# design.net
KiCad netlist of a schematic drawn in Altium Designer
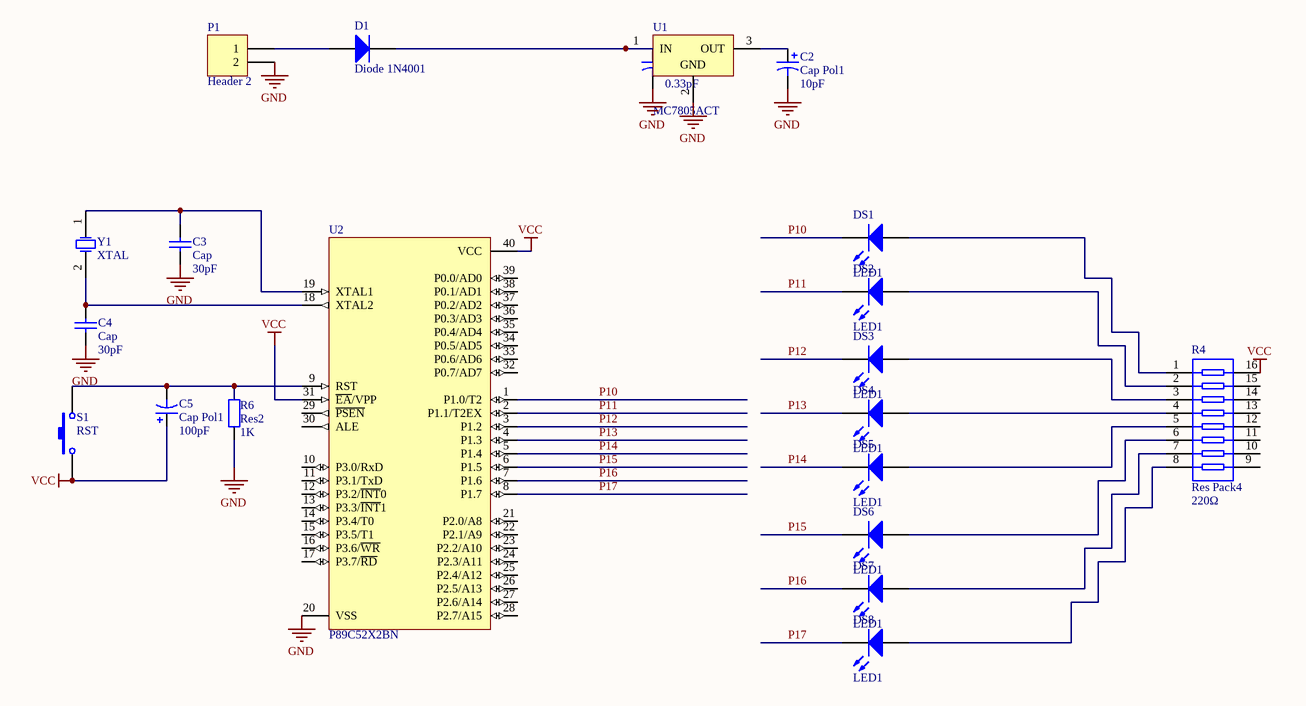
[diagram p0: 单片机控制流水灯电路.SchDoc]

(export (version "E")
  (design (tool "Eeschema 10.0.6"))
  (components
    (comp (ref "C1")
      (value "Cap Pol1")
      (footprint "RB7.6-15")
      (description "Polarized Capacitor (Radial)")
      (fields (field (name "ALTIUM_VALUE") "0.33pF") (field (name "PUBLISHER") "Altium Limited"))
      (libsource (lib "Miscellaneous Devices") (part "Cap Pol1"))
    )
    (comp (ref "C2")
      (value "Cap Pol1")
      (footprint "RB7.6-15")
      (description "Polarized Capacitor (Radial)")
      (fields (field (name "ALTIUM_VALUE") "10pF") (field (name "PUBLISHER") "Altium Limited"))
      (libsource (lib "Miscellaneous Devices") (part "Cap Pol1"))
    )
    (comp (ref "C3")
      (value "Cap")
      (footprint "RAD-0.3")
      (description "Capacitor")
      (fields (field (name "ALTIUM_VALUE") "30pF") (field (name "PUBLISHER") "Altium Limited"))
      (libsource (lib "Miscellaneous Devices") (part "Cap"))
    )
    (comp (ref "C4")
      (value "Cap")
      (footprint "RAD-0.3")
      (description "Capacitor")
      (fields (field (name "ALTIUM_VALUE") "30pF") (field (name "PUBLISHER") "Altium Limited"))
      (libsource (lib "Miscellaneous Devices") (part "Cap"))
    )
    (comp (ref "C5")
      (value "Cap Pol1")
      (footprint "RB7.6-15")
      (description "Polarized Capacitor (Radial)")
      (fields (field (name "ALTIUM_VALUE") "100pF") (field (name "PUBLISHER") "Altium Limited"))
      (libsource (lib "Miscellaneous Devices") (part "Cap Pol1"))
    )
    (comp (ref "D1")
      (value "Diode 1N4001")
      (footprint "DO-41")
      (description "1 Amp General Purpose Rectifier")
      (fields (field (name "PUBLISHER") "Altium Limited"))
      (libsource (lib "Miscellaneous Devices") (part "Diode 1N4001"))
    )
    (comp (ref "DS1")
      (value "LED1")
      (footprint "LED-1")
      (description "Typical RED GaAs LED")
      (fields (field (name "PUBLISHER") "Altium Limited"))
      (libsource (lib "Miscellaneous Devices") (part "LED1"))
    )
    (comp (ref "DS2")
      (value "LED1")
      (footprint "LED-1")
      (description "Typical RED GaAs LED")
      (fields (field (name "PUBLISHER") "Altium Limited"))
      (libsource (lib "Miscellaneous Devices") (part "LED1"))
    )
    (comp (ref "DS3")
      (value "LED1")
      (footprint "LED-1")
      (description "Typical RED GaAs LED")
      (fields (field (name "PUBLISHER") "Altium Limited"))
      (libsource (lib "Miscellaneous Devices") (part "LED1"))
    )
    (comp (ref "DS4")
      (value "LED1")
      (footprint "LED-1")
      (description "Typical RED GaAs LED")
      (fields (field (name "PUBLISHER") "Altium Limited"))
      (libsource (lib "Miscellaneous Devices") (part "LED1"))
    )
    (comp (ref "DS5")
      (value "LED1")
      (footprint "LED-1")
      (description "Typical RED GaAs LED")
      (fields (field (name "PUBLISHER") "Altium Limited"))
      (libsource (lib "Miscellaneous Devices") (part "LED1"))
    )
    (comp (ref "DS6")
      (value "LED1")
      (footprint "LED-1")
      (description "Typical RED GaAs LED")
      (fields (field (name "PUBLISHER") "Altium Limited"))
      (libsource (lib "Miscellaneous Devices") (part "LED1"))
    )
    (comp (ref "DS7")
      (value "LED1")
      (footprint "LED-1")
      (description "Typical RED GaAs LED")
      (fields (field (name "PUBLISHER") "Altium Limited"))
      (libsource (lib "Miscellaneous Devices") (part "LED1"))
    )
    (comp (ref "DS8")
      (value "LED1")
      (footprint "LED-1")
      (description "Typical RED GaAs LED")
      (fields (field (name "PUBLISHER") "Altium Limited"))
      (libsource (lib "Miscellaneous Devices") (part "LED1"))
    )
    (comp (ref "P1")
      (value "Header 2")
      (footprint "HDR1X2")
      (description "Header, 2-Pin")
      (fields (field (name "PUBLISHER") "Altium Limited"))
      (libsource (lib "Miscellaneous Connectors") (part "Header 2"))
    )
    (comp (ref "R4")
      (value "Res Pack4")
      (footprint "SSOP16_N")
      (description "Isolated Resistor Network")
      (fields (field (name "ALTIUM_VALUE") "220Ω") (field (name "PUBLISHER") "Altium Limited"))
      (libsource (lib "Miscellaneous Devices") (part "Res Pack4"))
    )
    (comp (ref "R6")
      (value "Res2")
      (footprint "AXIAL-0.4")
      (description "Resistor")
      (fields (field (name "ALTIUM_VALUE") "1K") (field (name "PUBLISHER") "Altium Limited"))
      (libsource (lib "Miscellaneous Devices") (part "Res2"))
    )
    (comp (ref "S1")
      (value "RST")
      (footprint "SPST-2")
      (description "Switch")
      (fields (field (name "PUBLISHER") "Altium Limited"))
      (libsource (lib "Miscellaneous Devices") (part "SW-PB"))
    )
    (comp (ref "U1")
      (value "MC7805ACT")
      (footprint "221A-04")
      (description "3-Terminal Positive Fixed Voltage Regulator")
      (fields (field (name "PUBLISHER") "Altium Limited"))
      (libsource (lib "Motorola Power Mgt Voltage Regulator") (part "MC7805ACT"))
    )
    (comp (ref "U2")
      (value "P89C52X2BN")
      (footprint "SOT129-1")
      (description "80C51 8-Bit Flash Microcontroller Family, 8 kB Flash")
      (fields (field (name "PUBLISHER") "Altium Limited"))
      (libsource (lib "Philips Microcontroller 8-Bit") (part "P89C52X2BN"))
    )
    (comp (ref "Y1")
      (value "XTAL")
      (footprint "R38")
      (description "Crystal Oscillator")
      (fields (field (name "PUBLISHER") "Altium Limited"))
      (libsource (lib "Miscellaneous Devices") (part "XTAL"))
    )
  )
  (nets
    (net (code "1") (name "/P10") (class "Default")
      (node (ref "DS1") (pin "2") (pinfunction "K_2") (pintype "passive"))
      (node (ref "U2") (pin "1") (pinfunction "P1.0/T2_1") (pintype "bidirectional"))
    )
    (net (code "2") (name "/P11") (class "Default")
      (node (ref "DS2") (pin "2") (pinfunction "K_2") (pintype "passive"))
      (node (ref "U2") (pin "2") (pinfunction "P1.1/T2EX_2") (pintype "bidirectional"))
    )
    (net (code "3") (name "/P12") (class "Default")
      (node (ref "DS3") (pin "2") (pinfunction "K_2") (pintype "passive"))
      (node (ref "U2") (pin "3") (pinfunction "P1.2_3") (pintype "bidirectional"))
    )
    (net (code "4") (name "/P13") (class "Default")
      (node (ref "DS4") (pin "2") (pinfunction "K_2") (pintype "passive"))
      (node (ref "U2") (pin "4") (pinfunction "P1.3_4") (pintype "bidirectional"))
    )
    (net (code "5") (name "/P14") (class "Default")
      (node (ref "DS5") (pin "2") (pinfunction "K_2") (pintype "passive"))
      (node (ref "U2") (pin "5") (pinfunction "P1.4_5") (pintype "bidirectional"))
    )
    (net (code "6") (name "/P15") (class "Default")
      (node (ref "DS6") (pin "2") (pinfunction "K_2") (pintype "passive"))
      (node (ref "U2") (pin "6") (pinfunction "P1.5_6") (pintype "bidirectional"))
    )
    (net (code "7") (name "/P16") (class "Default")
      (node (ref "DS7") (pin "2") (pinfunction "K_2") (pintype "passive"))
      (node (ref "U2") (pin "7") (pinfunction "P1.6_7") (pintype "bidirectional"))
    )
    (net (code "8") (name "/P17") (class "Default")
      (node (ref "DS8") (pin "2") (pinfunction "K_2") (pintype "passive"))
      (node (ref "U2") (pin "8") (pinfunction "P1.7_8") (pintype "bidirectional"))
    )
    (net (code "9") (name "GND") (class "Default")
      (node (ref "C1") (pin "2") (pinfunction "2_2") (pintype "passive"))
      (node (ref "C2") (pin "2") (pinfunction "2_2") (pintype "passive"))
      (node (ref "C3") (pin "1") (pinfunction "1_1") (pintype "passive"))
      (node (ref "C4") (pin "1") (pinfunction "1_1") (pintype "passive"))
      (node (ref "P1") (pin "2") (pinfunction "2_2") (pintype "passive"))
      (node (ref "R6") (pin "1") (pinfunction "1_1") (pintype "passive"))
      (node (ref "U1") (pin "2") (pinfunction "GND_2") (pintype "power_in"))
      (node (ref "U2") (pin "20") (pinfunction "VSS_20") (pintype "power_in"))
    )
    (net (code "10") (name "Net-(D1-A)") (class "Default")
      (node (ref "D1") (pin "1") (pinfunction "A_1") (pintype "passive"))
      (node (ref "P1") (pin "1") (pinfunction "1_1") (pintype "passive"))
    )
    (net (code "11") (name "Net-(D1-K)") (class "Default")
      (node (ref "C1") (pin "1") (pinfunction "1_1") (pintype "passive"))
      (node (ref "D1") (pin "2") (pinfunction "K_2") (pintype "passive"))
      (node (ref "U1") (pin "1") (pinfunction "IN_1") (pintype "power_in"))
    )
    (net (code "12") (name "Net-(DS1-A)") (class "Default")
      (node (ref "DS1") (pin "1") (pinfunction "A_1") (pintype "passive"))
      (node (ref "R4") (pin "1") (pinfunction "1_1") (pintype "passive"))
    )
    (net (code "13") (name "Net-(DS2-A)") (class "Default")
      (node (ref "DS2") (pin "1") (pinfunction "A_1") (pintype "passive"))
      (node (ref "R4") (pin "2") (pinfunction "2_2") (pintype "passive"))
    )
    (net (code "14") (name "Net-(DS3-A)") (class "Default")
      (node (ref "DS3") (pin "1") (pinfunction "A_1") (pintype "passive"))
      (node (ref "R4") (pin "3") (pinfunction "3_3") (pintype "passive"))
    )
    (net (code "15") (name "Net-(DS4-A)") (class "Default")
      (node (ref "DS4") (pin "1") (pinfunction "A_1") (pintype "passive"))
      (node (ref "R4") (pin "4") (pinfunction "4_4") (pintype "passive"))
    )
    (net (code "16") (name "Net-(DS5-A)") (class "Default")
      (node (ref "DS5") (pin "1") (pinfunction "A_1") (pintype "passive"))
      (node (ref "R4") (pin "5") (pinfunction "5_5") (pintype "passive"))
    )
    (net (code "17") (name "Net-(DS6-A)") (class "Default")
      (node (ref "DS6") (pin "1") (pinfunction "A_1") (pintype "passive"))
      (node (ref "R4") (pin "6") (pinfunction "6_6") (pintype "passive"))
    )
    (net (code "18") (name "Net-(DS7-A)") (class "Default")
      (node (ref "DS7") (pin "1") (pinfunction "A_1") (pintype "passive"))
      (node (ref "R4") (pin "7") (pinfunction "7_7") (pintype "passive"))
    )
    (net (code "19") (name "Net-(DS8-A)") (class "Default")
      (node (ref "DS8") (pin "1") (pinfunction "A_1") (pintype "passive"))
      (node (ref "R4") (pin "8") (pinfunction "8_8") (pintype "passive"))
    )
    (net (code "20") (name "Net-(U1-OUT)") (class "Default")
      (node (ref "C2") (pin "1") (pinfunction "1_1") (pintype "passive"))
      (node (ref "U1") (pin "3") (pinfunction "OUT_3") (pintype "power_in"))
    )
    (net (code "21") (name "Net-(U2-RST)") (class "Default")
      (node (ref "C5") (pin "2") (pinfunction "2_2") (pintype "passive"))
      (node (ref "R6") (pin "2") (pinfunction "2_2") (pintype "passive"))
      (node (ref "S1") (pin "2") (pinfunction "2_2") (pintype "passive"))
      (node (ref "U2") (pin "9") (pinfunction "RST_9") (pintype "input"))
    )
    (net (code "22") (name "Net-(U2-XTAL1)") (class "Default")
      (node (ref "C3") (pin "2") (pinfunction "2_2") (pintype "passive"))
      (node (ref "U2") (pin "19") (pinfunction "XTAL1_19") (pintype "input"))
      (node (ref "Y1") (pin "1") (pinfunction "OSC1_1") (pintype "passive"))
    )
    (net (code "23") (name "Net-(U2-XTAL2)") (class "Default")
      (node (ref "C4") (pin "2") (pinfunction "2_2") (pintype "passive"))
      (node (ref "U2") (pin "18") (pinfunction "XTAL2_18") (pintype "output"))
      (node (ref "Y1") (pin "2") (pinfunction "OSC2_2") (pintype "passive"))
    )
    (net (code "24") (name "VCC") (class "Default")
      (node (ref "C5") (pin "1") (pinfunction "1_1") (pintype "passive"))
      (node (ref "R4") (pin "16") (pinfunction "16_16") (pintype "passive"))
      (node (ref "S1") (pin "1") (pinfunction "1_1") (pintype "passive"))
      (node (ref "U2") (pin "31") (pinfunction "~{EA}/VPP_31") (pintype "input"))
      (node (ref "U2") (pin "40") (pinfunction "VCC_40") (pintype "power_in"))
    )
    (net (code "25") (name "unconnected-(R4-Pad9)") (class "Default")
      (node (ref "R4") (pin "9") (pinfunction "9_9") (pintype "passive"))
    )
    (net (code "26") (name "unconnected-(R4-Pad10)") (class "Default")
      (node (ref "R4") (pin "10") (pinfunction "10_10") (pintype "passive"))
    )
    (net (code "27") (name "unconnected-(R4-Pad11)") (class "Default")
      (node (ref "R4") (pin "11") (pinfunction "11_11") (pintype "passive"))
    )
    (net (code "28") (name "unconnected-(R4-Pad12)") (class "Default")
      (node (ref "R4") (pin "12") (pinfunction "12_12") (pintype "passive"))
    )
    (net (code "29") (name "unconnected-(R4-Pad13)") (class "Default")
      (node (ref "R4") (pin "13") (pinfunction "13_13") (pintype "passive"))
    )
    (net (code "30") (name "unconnected-(R4-Pad14)") (class "Default")
      (node (ref "R4") (pin "14") (pinfunction "14_14") (pintype "passive"))
    )
    (net (code "31") (name "unconnected-(R4-Pad15)") (class "Default")
      (node (ref "R4") (pin "15") (pinfunction "15_15") (pintype "passive"))
    )
    (net (code "32") (name "unconnected-(U2-ALE-Pad30)") (class "Default")
      (node (ref "U2") (pin "30") (pinfunction "ALE_30") (pintype "output"))
    )
    (net (code "33") (name "unconnected-(U2-P0.0{slash}AD0-Pad39)") (class "Default")
      (node (ref "U2") (pin "39") (pinfunction "P0.0/AD0_39") (pintype "bidirectional"))
    )
    (net (code "34") (name "unconnected-(U2-P0.1{slash}AD1-Pad38)") (class "Default")
      (node (ref "U2") (pin "38") (pinfunction "P0.1/AD1_38") (pintype "bidirectional"))
    )
    (net (code "35") (name "unconnected-(U2-P0.2{slash}AD2-Pad37)") (class "Default")
      (node (ref "U2") (pin "37") (pinfunction "P0.2/AD2_37") (pintype "bidirectional"))
    )
    (net (code "36") (name "unconnected-(U2-P0.3{slash}AD3-Pad36)") (class "Default")
      (node (ref "U2") (pin "36") (pinfunction "P0.3/AD3_36") (pintype "bidirectional"))
    )
    (net (code "37") (name "unconnected-(U2-P0.4{slash}AD4-Pad35)") (class "Default")
      (node (ref "U2") (pin "35") (pinfunction "P0.4/AD4_35") (pintype "bidirectional"))
    )
    (net (code "38") (name "unconnected-(U2-P0.5{slash}AD5-Pad34)") (class "Default")
      (node (ref "U2") (pin "34") (pinfunction "P0.5/AD5_34") (pintype "bidirectional"))
    )
    (net (code "39") (name "unconnected-(U2-P0.6{slash}AD6-Pad33)") (class "Default")
      (node (ref "U2") (pin "33") (pinfunction "P0.6/AD6_33") (pintype "bidirectional"))
    )
    (net (code "40") (name "unconnected-(U2-P0.7{slash}AD7-Pad32)") (class "Default")
      (node (ref "U2") (pin "32") (pinfunction "P0.7/AD7_32") (pintype "bidirectional"))
    )
    (net (code "41") (name "unconnected-(U2-P2.0{slash}A8-Pad21)") (class "Default")
      (node (ref "U2") (pin "21") (pinfunction "P2.0/A8_21") (pintype "bidirectional"))
    )
    (net (code "42") (name "unconnected-(U2-P2.1{slash}A9-Pad22)") (class "Default")
      (node (ref "U2") (pin "22") (pinfunction "P2.1/A9_22") (pintype "bidirectional"))
    )
    (net (code "43") (name "unconnected-(U2-P2.2{slash}A10-Pad23)") (class "Default")
      (node (ref "U2") (pin "23") (pinfunction "P2.2/A10_23") (pintype "bidirectional"))
    )
    (net (code "44") (name "unconnected-(U2-P2.3{slash}A11-Pad24)") (class "Default")
      (node (ref "U2") (pin "24") (pinfunction "P2.3/A11_24") (pintype "bidirectional"))
    )
    (net (code "45") (name "unconnected-(U2-P2.4{slash}A12-Pad25)") (class "Default")
      (node (ref "U2") (pin "25") (pinfunction "P2.4/A12_25") (pintype "bidirectional"))
    )
    (net (code "46") (name "unconnected-(U2-P2.5{slash}A13-Pad26)") (class "Default")
      (node (ref "U2") (pin "26") (pinfunction "P2.5/A13_26") (pintype "bidirectional"))
    )
    (net (code "47") (name "unconnected-(U2-P2.6{slash}A14-Pad27)") (class "Default")
      (node (ref "U2") (pin "27") (pinfunction "P2.6/A14_27") (pintype "bidirectional"))
    )
    (net (code "48") (name "unconnected-(U2-P2.7{slash}A15-Pad28)") (class "Default")
      (node (ref "U2") (pin "28") (pinfunction "P2.7/A15_28") (pintype "bidirectional"))
    )
    (net (code "49") (name "unconnected-(U2-P3.0{slash}RxD-Pad10)") (class "Default")
      (node (ref "U2") (pin "10") (pinfunction "P3.0/RxD_10") (pintype "bidirectional"))
    )
    (net (code "50") (name "unconnected-(U2-P3.1{slash}TxD-Pad11)") (class "Default")
      (node (ref "U2") (pin "11") (pinfunction "P3.1/TxD_11") (pintype "bidirectional"))
    )
    (net (code "51") (name "unconnected-(U2-P3.2{slash}~{INT}0-Pad12)") (class "Default")
      (node (ref "U2") (pin "12") (pinfunction "P3.2/~{INT}0_12") (pintype "bidirectional"))
    )
    (net (code "52") (name "unconnected-(U2-P3.3{slash}~{INT}1-Pad13)") (class "Default")
      (node (ref "U2") (pin "13") (pinfunction "P3.3/~{INT}1_13") (pintype "bidirectional"))
    )
    (net (code "53") (name "unconnected-(U2-P3.4{slash}T0-Pad14)") (class "Default")
      (node (ref "U2") (pin "14") (pinfunction "P3.4/T0_14") (pintype "bidirectional"))
    )
    (net (code "54") (name "unconnected-(U2-P3.5{slash}T1-Pad15)") (class "Default")
      (node (ref "U2") (pin "15") (pinfunction "P3.5/T1_15") (pintype "bidirectional"))
    )
    (net (code "55") (name "unconnected-(U2-P3.6{slash}~{WR}-Pad16)") (class "Default")
      (node (ref "U2") (pin "16") (pinfunction "P3.6/~{WR}_16") (pintype "bidirectional"))
    )
    (net (code "56") (name "unconnected-(U2-P3.7{slash}~{RD}-Pad17)") (class "Default")
      (node (ref "U2") (pin "17") (pinfunction "P3.7/~{RD}_17") (pintype "bidirectional"))
    )
    (net (code "57") (name "unconnected-(U2-~{PSEN}-Pad29)") (class "Default")
      (node (ref "U2") (pin "29") (pinfunction "~{PSEN}_29") (pintype "output"))
    )
  )
)
